# i2c_arduino.net
KiCad netlist of a schematic drawn in EAGLE
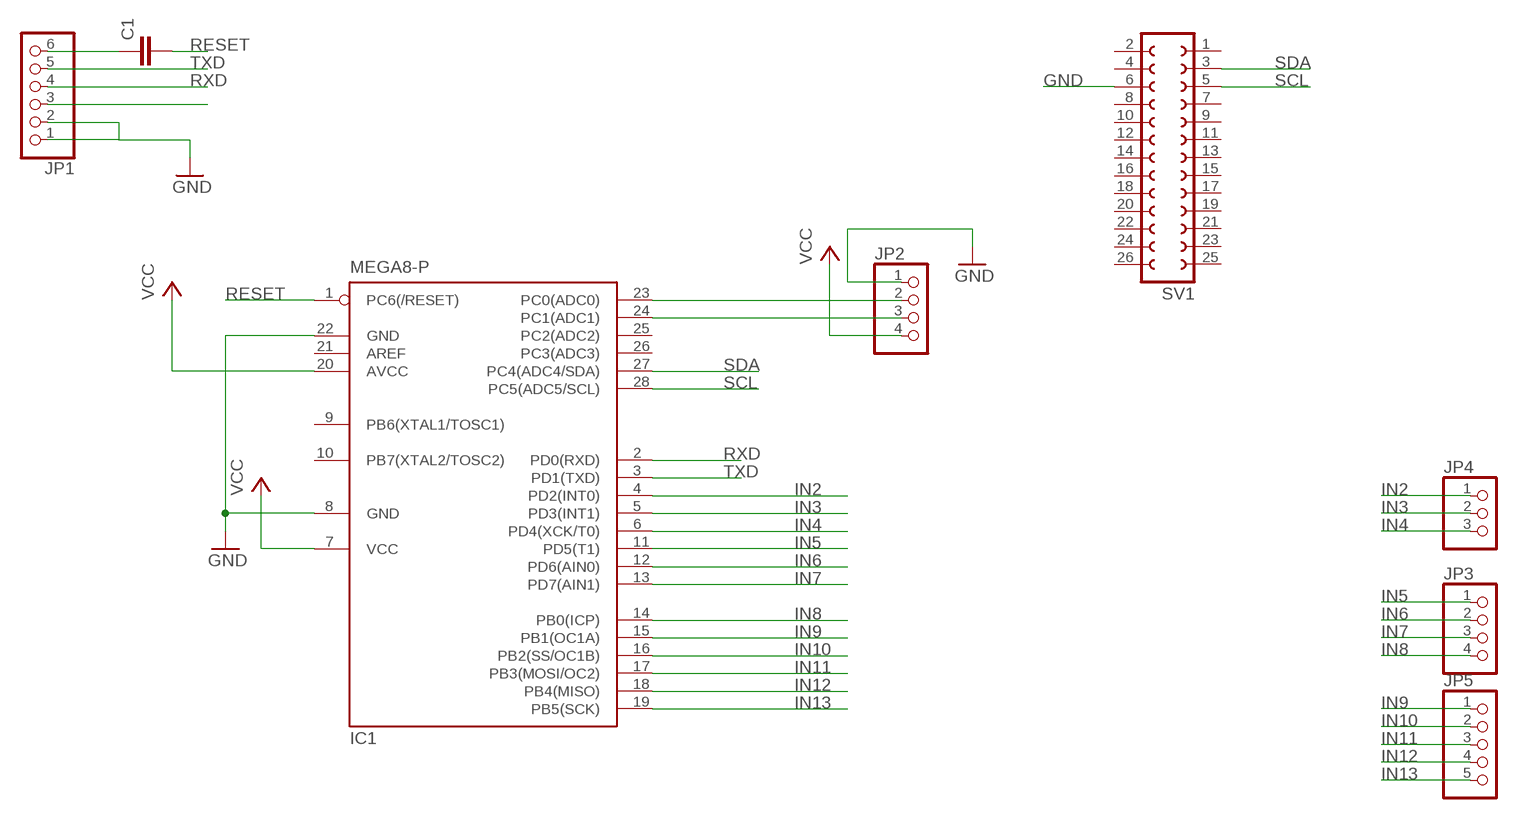
[diagram p0: schematic, sheet 1]

(export (version "E")
  (design (tool "Eeschema 10.0.6"))
  (components
    (comp (ref "C1")
      (value "C-EU025-025X050")
      (footprint "eagle-import:C025-025X050")
      (libsource (lib "eagle-import") (part "C-EU025-025X050"))
    )
    (comp (ref "IC1")
      (value "MEGA8-P")
      (footprint "eagle-import:DIL28-3")
      (libsource (lib "eagle-import") (part "MEGA8-P"))
    )
    (comp (ref "JP1")
      (value "PINHD-1X6/90")
      (footprint "eagle-import:1X06_90")
      (libsource (lib "eagle-import") (part "PINHD-1X6/90"))
    )
    (comp (ref "JP2")
      (value "PINHD-1X4")
      (footprint "eagle-import:1X04")
      (libsource (lib "eagle-import") (part "PINHD-1X4"))
    )
    (comp (ref "JP3")
      (value "PINHD-1X4")
      (footprint "eagle-import:1X04")
      (libsource (lib "eagle-import") (part "PINHD-1X4"))
    )
    (comp (ref "JP4")
      (value "PINHD-1X3")
      (footprint "eagle-import:1X03")
      (libsource (lib "eagle-import") (part "PINHD-1X3"))
    )
    (comp (ref "JP5")
      (value "PINHD-1X5")
      (footprint "eagle-import:1X05")
      (libsource (lib "eagle-import") (part "PINHD-1X5"))
    )
    (comp (ref "SV1")
      (value "FE13-2")
      (footprint "eagle-import:FE13-2")
      (libsource (lib "eagle-import") (part "FE13-2"))
    )
  )
  (nets
    (net (code "1") (name "/IN2") (class "Default")
      (node (ref "IC1") (pin "4") (pinfunction "PD2(INT0)_4") (pintype "bidirectional"))
      (node (ref "JP4") (pin "1") (pinfunction "1_1") (pintype "passive"))
    )
    (net (code "2") (name "/IN3") (class "Default")
      (node (ref "IC1") (pin "5") (pinfunction "PD3(INT1)_5") (pintype "bidirectional"))
      (node (ref "JP4") (pin "2") (pinfunction "2_2") (pintype "passive"))
    )
    (net (code "3") (name "/IN4") (class "Default")
      (node (ref "IC1") (pin "6") (pinfunction "PD4(XCK/T0)_6") (pintype "bidirectional"))
      (node (ref "JP4") (pin "3") (pinfunction "3_3") (pintype "passive"))
    )
    (net (code "4") (name "/IN5") (class "Default")
      (node (ref "IC1") (pin "11") (pinfunction "PD5(T1)_11") (pintype "bidirectional"))
      (node (ref "JP3") (pin "1") (pinfunction "1_1") (pintype "passive"))
    )
    (net (code "5") (name "/IN6") (class "Default")
      (node (ref "IC1") (pin "12") (pinfunction "PD6(AIN0)_12") (pintype "bidirectional"))
      (node (ref "JP3") (pin "2") (pinfunction "2_2") (pintype "passive"))
    )
    (net (code "6") (name "/IN7") (class "Default")
      (node (ref "IC1") (pin "13") (pinfunction "PD7(AIN1)_13") (pintype "bidirectional"))
      (node (ref "JP3") (pin "3") (pinfunction "3_3") (pintype "passive"))
    )
    (net (code "7") (name "/IN8") (class "Default")
      (node (ref "IC1") (pin "14") (pinfunction "PB0(ICP)_14") (pintype "bidirectional"))
      (node (ref "JP3") (pin "4") (pinfunction "4_4") (pintype "passive"))
    )
    (net (code "8") (name "/IN9") (class "Default")
      (node (ref "IC1") (pin "15") (pinfunction "PB1(OC1A)_15") (pintype "bidirectional"))
      (node (ref "JP5") (pin "1") (pinfunction "1_1") (pintype "passive"))
    )
    (net (code "9") (name "/IN10") (class "Default")
      (node (ref "IC1") (pin "16") (pinfunction "PB2(SS/OC1B)_16") (pintype "bidirectional"))
      (node (ref "JP5") (pin "2") (pinfunction "2_2") (pintype "passive"))
    )
    (net (code "10") (name "/IN11") (class "Default")
      (node (ref "IC1") (pin "17") (pinfunction "PB3(MOSI/OC2)_17") (pintype "bidirectional"))
      (node (ref "JP5") (pin "3") (pinfunction "3_3") (pintype "passive"))
    )
    (net (code "11") (name "/IN12") (class "Default")
      (node (ref "IC1") (pin "18") (pinfunction "PB4(MISO)_18") (pintype "bidirectional"))
      (node (ref "JP5") (pin "4") (pinfunction "4_4") (pintype "passive"))
    )
    (net (code "12") (name "/IN13") (class "Default")
      (node (ref "IC1") (pin "19") (pinfunction "PB5(SCK)_19") (pintype "bidirectional"))
      (node (ref "JP5") (pin "5") (pinfunction "5_5") (pintype "passive"))
    )
    (net (code "13") (name "/RESET") (class "Default")
      (node (ref "C1") (pin "2") (pinfunction "2_2") (pintype "passive"))
      (node (ref "IC1") (pin "1") (pinfunction "PC6(/RESET)_1") (pintype "bidirectional"))
    )
    (net (code "14") (name "/RXD") (class "Default")
      (node (ref "IC1") (pin "2") (pinfunction "PD0(RXD)_2") (pintype "bidirectional"))
      (node (ref "JP1") (pin "4") (pinfunction "4_4") (pintype "passive"))
    )
    (net (code "15") (name "/SCL") (class "Default")
      (node (ref "IC1") (pin "28") (pinfunction "PC5(ADC5/SCL)_28") (pintype "bidirectional"))
      (node (ref "SV1") (pin "5") (pinfunction "5_5") (pintype "passive"))
    )
    (net (code "16") (name "/SDA") (class "Default")
      (node (ref "IC1") (pin "27") (pinfunction "PC4(ADC4/SDA)_27") (pintype "bidirectional"))
      (node (ref "SV1") (pin "3") (pinfunction "3_3") (pintype "passive"))
    )
    (net (code "17") (name "/TXD") (class "Default")
      (node (ref "IC1") (pin "3") (pinfunction "PD1(TXD)_3") (pintype "bidirectional"))
      (node (ref "JP1") (pin "5") (pinfunction "5_5") (pintype "passive"))
    )
    (net (code "18") (name "GND") (class "Default")
      (node (ref "IC1") (pin "22") (pinfunction "GND_22") (pintype "power_in"))
      (node (ref "IC1") (pin "8") (pinfunction "GND_8") (pintype "power_in"))
      (node (ref "JP1") (pin "1") (pinfunction "1_1") (pintype "passive"))
      (node (ref "JP1") (pin "2") (pinfunction "2_2") (pintype "passive"))
      (node (ref "JP2") (pin "1") (pinfunction "1_1") (pintype "passive"))
      (node (ref "SV1") (pin "6") (pinfunction "6_6") (pintype "passive"))
    )
    (net (code "19") (name "Net-(C1-Pad1)") (class "Default")
      (node (ref "C1") (pin "1") (pinfunction "1_1") (pintype "passive"))
      (node (ref "JP1") (pin "6") (pinfunction "6_6") (pintype "passive"))
    )
    (net (code "20") (name "Net-(IC1-PC0(ADC0))") (class "Default")
      (node (ref "IC1") (pin "23") (pinfunction "PC0(ADC0)_23") (pintype "bidirectional"))
      (node (ref "JP2") (pin "2") (pinfunction "2_2") (pintype "passive"))
    )
    (net (code "21") (name "Net-(IC1-PC1(ADC1))") (class "Default")
      (node (ref "IC1") (pin "24") (pinfunction "PC1(ADC1)_24") (pintype "bidirectional"))
      (node (ref "JP2") (pin "3") (pinfunction "3_3") (pintype "passive"))
    )
    (net (code "22") (name "VCC") (class "Default")
      (node (ref "IC1") (pin "20") (pinfunction "AVCC_20") (pintype "power_in"))
      (node (ref "IC1") (pin "7") (pinfunction "VCC_7") (pintype "power_in"))
      (node (ref "JP1") (pin "3") (pinfunction "3_3") (pintype "passive"))
      (node (ref "JP2") (pin "4") (pinfunction "4_4") (pintype "passive"))
    )
    (net (code "23") (name "unconnected-(IC1-AREF-Pad21)") (class "Default")
      (node (ref "IC1") (pin "21") (pinfunction "AREF_21") (pintype "passive"))
    )
    (net (code "24") (name "unconnected-(IC1-PB6(XTAL1{slash}TOSC1)-Pad9)") (class "Default")
      (node (ref "IC1") (pin "9") (pinfunction "PB6(XTAL1/TOSC1)_9") (pintype "bidirectional"))
    )
    (net (code "25") (name "unconnected-(IC1-PB7(XTAL2{slash}TOSC2)-Pad10)") (class "Default")
      (node (ref "IC1") (pin "10") (pinfunction "PB7(XTAL2/TOSC2)_10") (pintype "bidirectional"))
    )
    (net (code "26") (name "unconnected-(IC1-PC2(ADC2)-Pad25)") (class "Default")
      (node (ref "IC1") (pin "25") (pinfunction "PC2(ADC2)_25") (pintype "bidirectional"))
    )
    (net (code "27") (name "unconnected-(IC1-PC3(ADC3)-Pad26)") (class "Default")
      (node (ref "IC1") (pin "26") (pinfunction "PC3(ADC3)_26") (pintype "bidirectional"))
    )
    (net (code "28") (name "unconnected-(SV1-Pad1)") (class "Default")
      (node (ref "SV1") (pin "1") (pinfunction "1_1") (pintype "passive"))
    )
    (net (code "29") (name "unconnected-(SV1-Pad2)") (class "Default")
      (node (ref "SV1") (pin "2") (pinfunction "2_2") (pintype "passive"))
    )
    (net (code "30") (name "unconnected-(SV1-Pad4)") (class "Default")
      (node (ref "SV1") (pin "4") (pinfunction "4_4") (pintype "passive"))
    )
    (net (code "31") (name "unconnected-(SV1-Pad7)") (class "Default")
      (node (ref "SV1") (pin "7") (pinfunction "7_7") (pintype "passive"))
    )
    (net (code "32") (name "unconnected-(SV1-Pad8)") (class "Default")
      (node (ref "SV1") (pin "8") (pinfunction "8_8") (pintype "passive"))
    )
    (net (code "33") (name "unconnected-(SV1-Pad9)") (class "Default")
      (node (ref "SV1") (pin "9") (pinfunction "9_9") (pintype "passive"))
    )
    (net (code "34") (name "unconnected-(SV1-Pad10)") (class "Default")
      (node (ref "SV1") (pin "10") (pinfunction "10_10") (pintype "passive"))
    )
    (net (code "35") (name "unconnected-(SV1-Pad11)") (class "Default")
      (node (ref "SV1") (pin "11") (pinfunction "11_11") (pintype "passive"))
    )
    (net (code "36") (name "unconnected-(SV1-Pad12)") (class "Default")
      (node (ref "SV1") (pin "12") (pinfunction "12_12") (pintype "passive"))
    )
    (net (code "37") (name "unconnected-(SV1-Pad13)") (class "Default")
      (node (ref "SV1") (pin "13") (pinfunction "13_13") (pintype "passive"))
    )
    (net (code "38") (name "unconnected-(SV1-Pad14)") (class "Default")
      (node (ref "SV1") (pin "14") (pinfunction "14_14") (pintype "passive"))
    )
    (net (code "39") (name "unconnected-(SV1-Pad15)") (class "Default")
      (node (ref "SV1") (pin "15") (pinfunction "15_15") (pintype "passive"))
    )
    (net (code "40") (name "unconnected-(SV1-Pad16)") (class "Default")
      (node (ref "SV1") (pin "16") (pinfunction "16_16") (pintype "passive"))
    )
    (net (code "41") (name "unconnected-(SV1-Pad17)") (class "Default")
      (node (ref "SV1") (pin "17") (pinfunction "17_17") (pintype "passive"))
    )
    (net (code "42") (name "unconnected-(SV1-Pad18)") (class "Default")
      (node (ref "SV1") (pin "18") (pinfunction "18_18") (pintype "passive"))
    )
    (net (code "43") (name "unconnected-(SV1-Pad19)") (class "Default")
      (node (ref "SV1") (pin "19") (pinfunction "19_19") (pintype "passive"))
    )
    (net (code "44") (name "unconnected-(SV1-Pad20)") (class "Default")
      (node (ref "SV1") (pin "20") (pinfunction "20_20") (pintype "passive"))
    )
    (net (code "45") (name "unconnected-(SV1-Pad21)") (class "Default")
      (node (ref "SV1") (pin "21") (pinfunction "21_21") (pintype "passive"))
    )
    (net (code "46") (name "unconnected-(SV1-Pad22)") (class "Default")
      (node (ref "SV1") (pin "22") (pinfunction "22_22") (pintype "passive"))
    )
    (net (code "47") (name "unconnected-(SV1-Pad23)") (class "Default")
      (node (ref "SV1") (pin "23") (pinfunction "23_23") (pintype "passive"))
    )
    (net (code "48") (name "unconnected-(SV1-Pad24)") (class "Default")
      (node (ref "SV1") (pin "24") (pinfunction "24_24") (pintype "passive"))
    )
    (net (code "49") (name "unconnected-(SV1-Pad25)") (class "Default")
      (node (ref "SV1") (pin "25") (pinfunction "25_25") (pintype "passive"))
    )
    (net (code "50") (name "unconnected-(SV1-Pad26)") (class "Default")
      (node (ref "SV1") (pin "26") (pinfunction "26_26") (pintype "passive"))
    )
  )
)
